# design.net
KiCad netlist of a schematic drawn in EasyEDA Pro
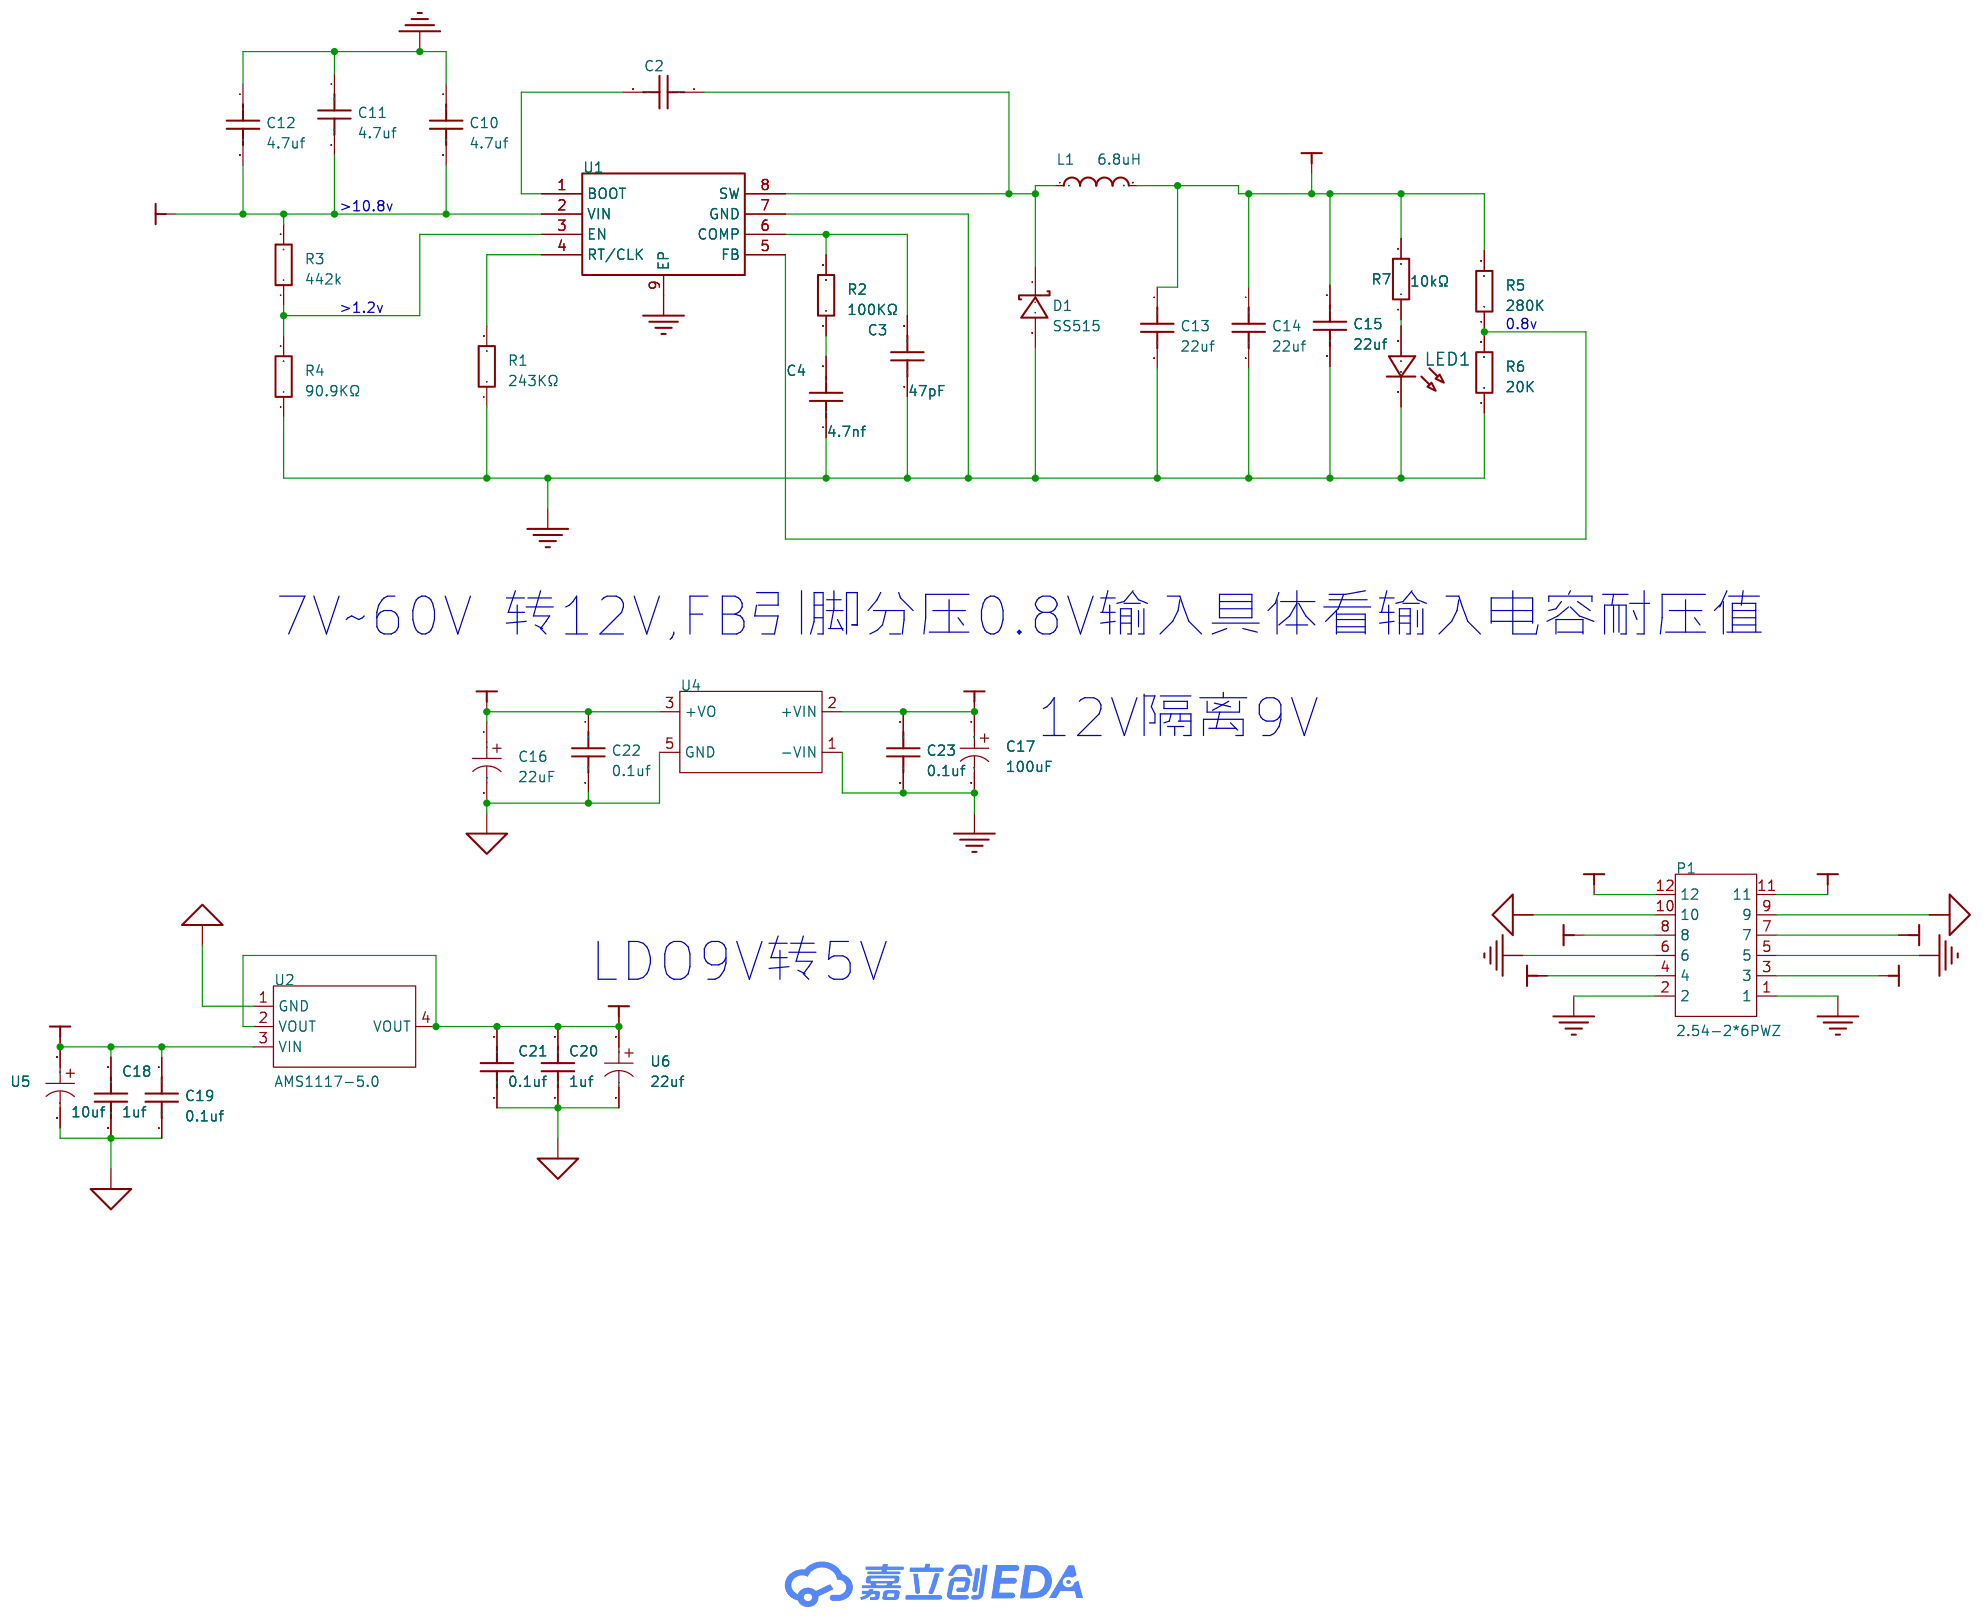
[diagram p0: schematic sheet]

(export (version "E")
  (design (tool "Eeschema 10.0.6"))
  (components
    (comp (ref "C2")
      (value "100nF")
      (footprint "easyedapro:C0603")
      (libsource (lib "easyedapro") (part "Capacitance"))
    )
    (comp (ref "C3")
      (value "47pF")
      (footprint "easyedapro:C0603")
      (libsource (lib "easyedapro") (part "Capacitance"))
    )
    (comp (ref "C4")
      (value "4.7nf")
      (footprint "easyedapro:C0603")
      (libsource (lib "easyedapro") (part "Capacitance"))
    )
    (comp (ref "C10")
      (value "4.7uf")
      (footprint "easyedapro:C0603")
      (libsource (lib "easyedapro") (part "Capacitance"))
    )
    (comp (ref "C11")
      (value "4.7uf")
      (footprint "easyedapro:C0603")
      (libsource (lib "easyedapro") (part "Capacitance"))
    )
    (comp (ref "C12")
      (value "4.7uf")
      (footprint "easyedapro:C0603")
      (libsource (lib "easyedapro") (part "Capacitance"))
    )
    (comp (ref "C13")
      (value "22uf")
      (footprint "easyedapro:C0603")
      (libsource (lib "easyedapro") (part "Capacitance"))
    )
    (comp (ref "C14")
      (value "22uf")
      (footprint "easyedapro:C0603")
      (libsource (lib "easyedapro") (part "Capacitance"))
    )
    (comp (ref "C15")
      (value "22uf")
      (footprint "easyedapro:C0603")
      (libsource (lib "easyedapro") (part "Capacitance"))
    )
    (comp (ref "C16")
      (value "22uF")
      (footprint "easyedapro:CAP-TH_BD8.0-P3.50-D0.6-FD_1")
      (description "容值:22uF;精度:±20%;额定电压:160V;纹波电流:-;等效串联电阻(ESR):-;")
      (fields (field (name "Manufacturer Part") "EGW2CM220F12OT") (field (name "Manufacturer") "AISHI(艾华集团)"))
      (libsource (lib "easyedapro") (part "EGW2CM220F12OT"))
    )
    (comp (ref "C17")
      (value "100uF")
      (footprint "easyedapro:CAP-TH_BD10.0-P5.00-D0.6-FD_H16.0")
      (description "容值:100uF;精度:±20%;额定电压:100V;")
      (fields
        (field (name "Manufacturer Part") "ERA100V100M10X16")
        (field (name "Manufacturer") "JIERR(捷而瑞)")
      )
      (libsource (lib "easyedapro") (part "ERA100V100M10X16"))
    )
    (comp (ref "C18")
      (value "1uf")
      (footprint "easyedapro:C0603")
      (libsource (lib "easyedapro") (part "Capacitance"))
    )
    (comp (ref "C19")
      (value "0.1uf")
      (footprint "easyedapro:C0603")
      (libsource (lib "easyedapro") (part "Capacitance"))
    )
    (comp (ref "C20")
      (value "1uf")
      (footprint "easyedapro:C0603")
      (libsource (lib "easyedapro") (part "Capacitance"))
    )
    (comp (ref "C21")
      (value "0.1uf")
      (footprint "easyedapro:C0603")
      (libsource (lib "easyedapro") (part "Capacitance"))
    )
    (comp (ref "C22")
      (value "0.1uf")
      (footprint "easyedapro:C0603")
      (libsource (lib "easyedapro") (part "Capacitance"))
    )
    (comp (ref "C23")
      (value "0.1uf")
      (footprint "easyedapro:C0603")
      (libsource (lib "easyedapro") (part "Capacitance"))
    )
    (comp (ref "D1")
      (value "SS515")
      (footprint "easyedapro:SMA_L4.3-W2.6-LS5.2-RD")
      (description "正向压降(Vf):950mV@3A;直流反向耐压(Vr):200V;平均整流电流(Io):3A;")
      (fields (field (name "Manufacturer") "MDD"))
      (libsource (lib "easyedapro") (part "SS3200_C65001"))
    )
    (comp (ref "L1")
      (value "6.8uH")
      (footprint "easyedapro:IND-SMD_L7.1-W6.6")
      (description "电感值:10uH;精度:±20%;饱和电流(Isat):4.5A;类型:一体成型电感;")
      (fields (field (name "Manufacturer Part") "D0630HP-100MT") (field (name "Manufacturer") "DEYAN(德砚电子)"))
      (libsource (lib "easyedapro") (part "D0630HP-100MT"))
    )
    (comp (ref "LED1")
      (value "~")
      (footprint "easyedapro:LED_0603")
      (libsource (lib "easyedapro") (part "LED_R"))
    )
    (comp (ref "P1")
      (value "2.54-2*6PWZ")
      (footprint "easyedapro:HDR-TH_12P-P2.54-H-M-R2-C6-S2.54-W12.5")
      (fields (field (name "Manufacturer") "BOOMELE(博穆精密)"))
      (libsource (lib "easyedapro") (part "2*6P header"))
    )
    (comp (ref "R1")
      (value "243KΩ")
      (footprint "easyedapro:R0603")
      (libsource (lib "easyedapro") (part "电阻_1"))
    )
    (comp (ref "R2")
      (value "100KΩ")
      (footprint "easyedapro:R0603")
      (libsource (lib "easyedapro") (part "电阻_1"))
    )
    (comp (ref "R3")
      (value "442k")
      (footprint "easyedapro:R0603")
      (libsource (lib "easyedapro") (part "电阻_1"))
    )
    (comp (ref "R4")
      (value "90.9KΩ")
      (footprint "easyedapro:R0603")
      (libsource (lib "easyedapro") (part "电阻_1"))
    )
    (comp (ref "R5")
      (value "280K")
      (footprint "easyedapro:R0603")
      (libsource (lib "easyedapro") (part "电阻_1"))
    )
    (comp (ref "R6")
      (value "20K")
      (footprint "easyedapro:R0603")
      (libsource (lib "easyedapro") (part "电阻_1"))
    )
    (comp (ref "R7")
      (value "10kΩ")
      (footprint "easyedapro:R0805")
      (description "电阻类型:厚膜电阻;阻值:5.1kΩ;精度:±1%;功率:125mW;最大工作电压:150V;温度系数:±100ppm/℃;")
      (fields
        (field (name "Manufacturer Part") "0805W8F5101T5E")
        (field (name "Manufacturer") "UNI-ROYAL(厚声)")
      )
      (libsource (lib "easyedapro") (part "0805W8F5101T5E"))
    )
    (comp (ref "U1")
      (value "TPS54560DDAR")
      (footprint "easyedapro:SOIC-8_L5.0-W4.0-P1.27-LS6.0-BL-EP2.0")
      (description "功能类型:降压型;输出类型:可调;工作电压:4.5V~60V;输出电压:800mV~58.8V;输出电流:5A;")
      (fields (field (name "Manufacturer") "TI(德州仪器)"))
      (libsource (lib "easyedapro") (part "TPS54560DDAR"))
    )
    (comp (ref "U2")
      (value "AMS1117-5.0")
      (footprint "easyedapro:SOT-223_L6.5-W3.5-P2.30-LS7.0-BR")
      (description "输出类型:固定;工作电压:15V;输出电压:5V;输出电流:1A;电源纹波抑制比(PSRR):60dB;输出极性:正极;")
      (fields (field (name "Manufacturer") "AMS"))
      (libsource (lib "easyedapro") (part "AMS1117-5.0"))
    )
    (comp (ref "U4")
      (value "250kHz")
      (footprint "easyedapro:PWRM-TH_HI-LINK_VRBXXYMD-5WR3-1")
      (fields
        (field (name "Manufacturer Part") "VRB1205YMD-5WR3")
        (field (name "Manufacturer") "HI-LINK(海凌科)")
      )
      (libsource (lib "easyedapro") (part "VRB1205YMD-5WR3"))
    )
    (comp (ref "U5")
      (value "10uf")
      (footprint "easyedapro:CAP-SMD_L3.5-W2.8-FD")
      (libsource (lib "easyedapro") (part "贴片钽电容100UF+-20%6.3VB型"))
    )
    (comp (ref "U6")
      (value "22uf")
      (footprint "easyedapro:CAP-SMD_L3.5-W2.8-FD")
      (libsource (lib "easyedapro") (part "贴片钽电容100UF+-20%6.3VB型"))
    )
  )
  (nets
    (net (code "1") (name "+5V") (class "Default")
      (node (ref "C20") (pin "1") (pinfunction "1_1") (pintype "input"))
      (node (ref "C21") (pin "1") (pinfunction "1_1") (pintype "input"))
      (node (ref "P1") (pin "11") (pinfunction "11_11") (pintype "unspecified"))
      (node (ref "P1") (pin "12") (pinfunction "12_12") (pintype "unspecified"))
      (node (ref "U2") (pin "2") (pinfunction "VOUT_2") (pintype "unspecified"))
      (node (ref "U2") (pin "4") (pinfunction "VOUT_4") (pintype "unspecified"))
      (node (ref "U6") (pin "1") (pinfunction "1_1") (pintype "input"))
    )
    (net (code "2") (name "+9V") (class "Default")
      (node (ref "C16") (pin "1") (pinfunction "1_1") (pintype "input"))
      (node (ref "C18") (pin "1") (pinfunction "1_1") (pintype "input"))
      (node (ref "C19") (pin "1") (pinfunction "1_1") (pintype "input"))
      (node (ref "C22") (pin "1") (pinfunction "1_1") (pintype "input"))
      (node (ref "U2") (pin "3") (pinfunction "VIN_3") (pintype "unspecified"))
      (node (ref "U4") (pin "3") (pinfunction "+VO_3") (pintype "unspecified"))
      (node (ref "U5") (pin "1") (pinfunction "1_1") (pintype "input"))
    )
    (net (code "3") (name "+12V") (class "Default")
      (node (ref "C13") (pin "1") (pinfunction "1_1") (pintype "input"))
      (node (ref "C14") (pin "1") (pinfunction "1_1") (pintype "input"))
      (node (ref "C15") (pin "1") (pinfunction "1_1") (pintype "input"))
      (node (ref "C17") (pin "1") (pinfunction "1_1") (pintype "input"))
      (node (ref "C23") (pin "1") (pinfunction "1_1") (pintype "input"))
      (node (ref "L1") (pin "2") (pinfunction "2_2") (pintype "unspecified"))
      (node (ref "P1") (pin "7") (pinfunction "7_7") (pintype "unspecified"))
      (node (ref "P1") (pin "8") (pinfunction "8_8") (pintype "unspecified"))
      (node (ref "R5") (pin "2") (pinfunction "2_2") (pintype "input"))
      (node (ref "R7") (pin "2") (pinfunction "2_2") (pintype "input"))
      (node (ref "U4") (pin "2") (pinfunction "+VIN_2") (pintype "unspecified"))
    )
    (net (code "4") (name "AGND") (class "Default")
      (node (ref "C16") (pin "2") (pinfunction "2_2") (pintype "input"))
      (node (ref "C18") (pin "2") (pinfunction "2_2") (pintype "input"))
      (node (ref "C19") (pin "2") (pinfunction "2_2") (pintype "input"))
      (node (ref "C20") (pin "2") (pinfunction "2_2") (pintype "input"))
      (node (ref "C21") (pin "2") (pinfunction "2_2") (pintype "input"))
      (node (ref "C22") (pin "2") (pinfunction "2_2") (pintype "input"))
      (node (ref "P1") (pin "10") (pinfunction "10_10") (pintype "unspecified"))
      (node (ref "P1") (pin "9") (pinfunction "9_9") (pintype "unspecified"))
      (node (ref "U2") (pin "1") (pinfunction "GND_1") (pintype "unspecified"))
      (node (ref "U4") (pin "5") (pinfunction "GND_5") (pintype "unspecified"))
      (node (ref "U5") (pin "2") (pinfunction "2_2") (pintype "input"))
      (node (ref "U6") (pin "2") (pinfunction "2_2") (pintype "input"))
    )
    (net (code "5") (name "GND") (class "Default")
      (node (ref "C10") (pin "1") (pinfunction "1_1") (pintype "input"))
      (node (ref "C11") (pin "1") (pinfunction "1_1") (pintype "input"))
      (node (ref "C12") (pin "1") (pinfunction "1_1") (pintype "input"))
      (node (ref "C13") (pin "2") (pinfunction "2_2") (pintype "input"))
      (node (ref "C14") (pin "2") (pinfunction "2_2") (pintype "input"))
      (node (ref "C15") (pin "2") (pinfunction "2_2") (pintype "input"))
      (node (ref "C17") (pin "2") (pinfunction "2_2") (pintype "input"))
      (node (ref "C23") (pin "2") (pinfunction "2_2") (pintype "input"))
      (node (ref "C3") (pin "1") (pinfunction "1_1") (pintype "input"))
      (node (ref "C4") (pin "1") (pinfunction "1_1") (pintype "input"))
      (node (ref "D1") (pin "2") (pinfunction "A_2") (pintype "unspecified"))
      (node (ref "LED1") (pin "1") (pinfunction "C_1") (pintype "input"))
      (node (ref "P1") (pin "1") (pinfunction "1_1") (pintype "unspecified"))
      (node (ref "P1") (pin "2") (pinfunction "2_2") (pintype "unspecified"))
      (node (ref "P1") (pin "5") (pinfunction "5_5") (pintype "unspecified"))
      (node (ref "P1") (pin "6") (pinfunction "6_6") (pintype "unspecified"))
      (node (ref "R1") (pin "1") (pinfunction "1_1") (pintype "input"))
      (node (ref "R4") (pin "1") (pinfunction "1_1") (pintype "input"))
      (node (ref "R6") (pin "1") (pinfunction "1_1") (pintype "input"))
      (node (ref "U1") (pin "7") (pinfunction "GND_7") (pintype "unspecified"))
      (node (ref "U1") (pin "9") (pinfunction "EP_9") (pintype "unspecified"))
      (node (ref "U4") (pin "1") (pinfunction "-VIN_1") (pintype "unspecified"))
    )
    (net (code "6") (name "Net-(C4-Pad2)") (class "Default")
      (node (ref "C4") (pin "2") (pinfunction "2_2") (pintype "input"))
      (node (ref "R2") (pin "1") (pinfunction "1_1") (pintype "input"))
    )
    (net (code "7") (name "Net-(D1-K)") (class "Default")
      (node (ref "C2") (pin "1") (pinfunction "1_1") (pintype "input"))
      (node (ref "D1") (pin "1") (pinfunction "K_1") (pintype "unspecified"))
      (node (ref "L1") (pin "1") (pinfunction "1_1") (pintype "unspecified"))
      (node (ref "U1") (pin "8") (pinfunction "SW_8") (pintype "unspecified"))
    )
    (net (code "8") (name "Net-(LED1-A)") (class "Default")
      (node (ref "LED1") (pin "2") (pinfunction "A_2") (pintype "input"))
      (node (ref "R7") (pin "1") (pinfunction "1_1") (pintype "input"))
    )
    (net (code "9") (name "Net-(U1-BOOT)") (class "Default")
      (node (ref "C2") (pin "2") (pinfunction "2_2") (pintype "input"))
      (node (ref "U1") (pin "1") (pinfunction "BOOT_1") (pintype "unspecified"))
    )
    (net (code "10") (name "Net-(U1-COMP)") (class "Default")
      (node (ref "C3") (pin "2") (pinfunction "2_2") (pintype "input"))
      (node (ref "R2") (pin "2") (pinfunction "2_2") (pintype "input"))
      (node (ref "U1") (pin "6") (pinfunction "COMP_6") (pintype "unspecified"))
    )
    (net (code "11") (name "Net-(U1-EN)") (class "Default")
      (node (ref "R3") (pin "1") (pinfunction "1_1") (pintype "input"))
      (node (ref "R4") (pin "2") (pinfunction "2_2") (pintype "input"))
      (node (ref "U1") (pin "3") (pinfunction "EN_3") (pintype "unspecified"))
    )
    (net (code "12") (name "Net-(U1-FB)") (class "Default")
      (node (ref "R5") (pin "1") (pinfunction "1_1") (pintype "input"))
      (node (ref "R6") (pin "2") (pinfunction "2_2") (pintype "input"))
      (node (ref "U1") (pin "5") (pinfunction "FB_5") (pintype "unspecified"))
    )
    (net (code "13") (name "Net-(U1-RT{slash}CLK)") (class "Default")
      (node (ref "R1") (pin "2") (pinfunction "2_2") (pintype "input"))
      (node (ref "U1") (pin "4") (pinfunction "RT/CLK_4") (pintype "unspecified"))
    )
    (net (code "14") (name "VCC_IN") (class "Default")
      (node (ref "C10") (pin "2") (pinfunction "2_2") (pintype "input"))
      (node (ref "C11") (pin "2") (pinfunction "2_2") (pintype "input"))
      (node (ref "C12") (pin "2") (pinfunction "2_2") (pintype "input"))
      (node (ref "P1") (pin "3") (pinfunction "3_3") (pintype "unspecified"))
      (node (ref "P1") (pin "4") (pinfunction "4_4") (pintype "unspecified"))
      (node (ref "R3") (pin "2") (pinfunction "2_2") (pintype "input"))
      (node (ref "U1") (pin "2") (pinfunction "VIN_2") (pintype "unspecified"))
    )
  )
)
